# untitled.net
KiCad netlist of a schematic drawn in EAGLE
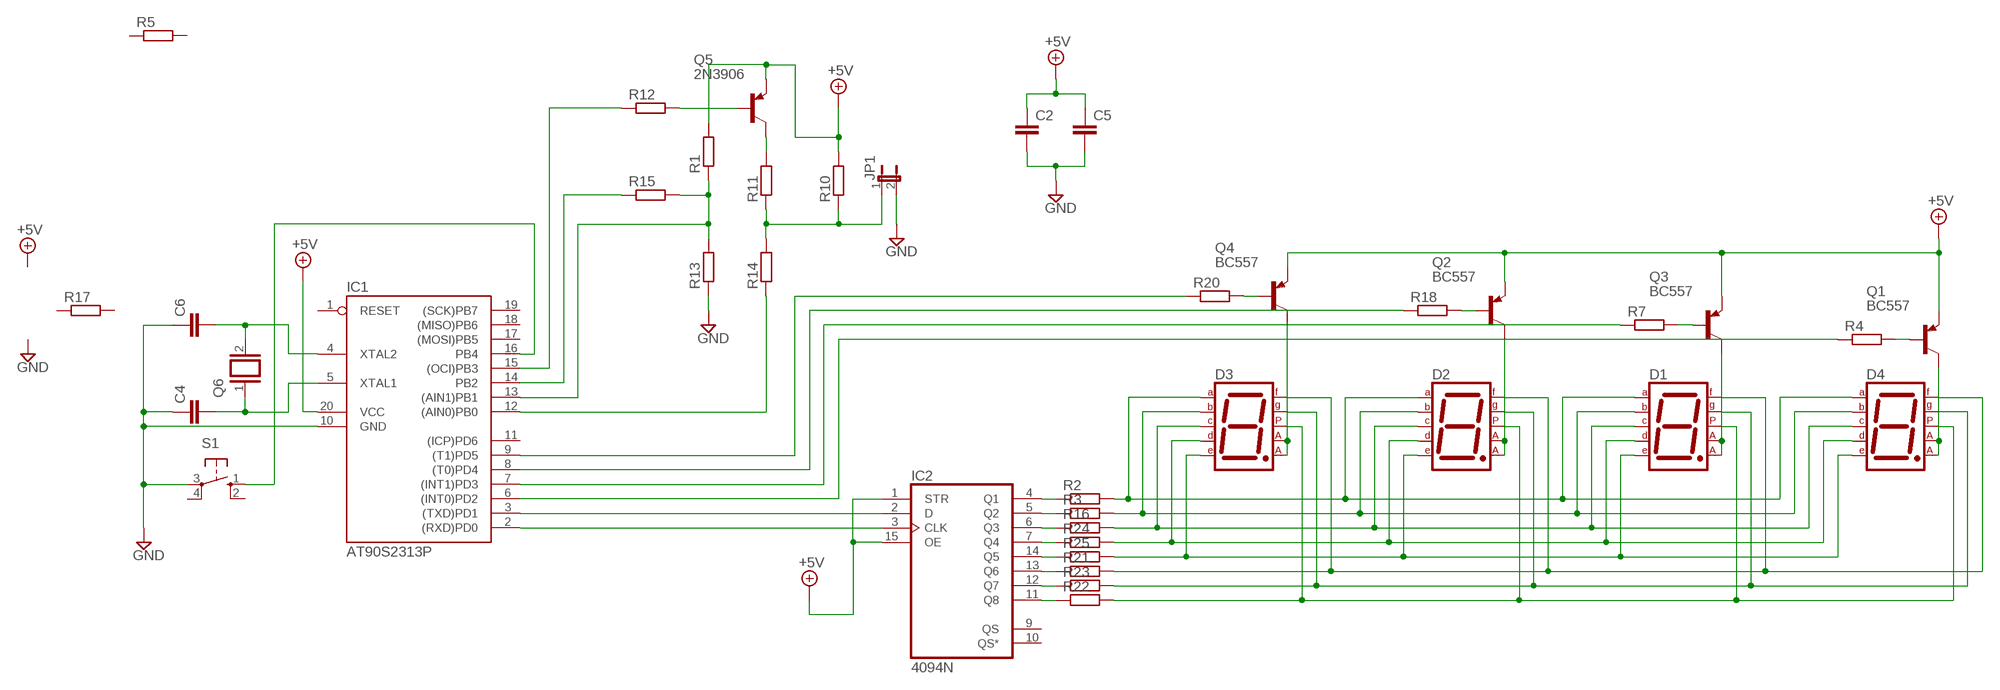
[diagram p0: schematic, sheet 1]

(export (version "E")
  (design (tool "Eeschema 10.0.6"))
  (components
    (comp (ref "C2")
      (value "C-EU025-025X050")
      (footprint "eagle-import:C025-025X050")
      (libsource (lib "eagle-import") (part "C-EU025-025X050"))
    )
    (comp (ref "C4")
      (value "C-EU025-025X050")
      (footprint "eagle-import:C025-025X050")
      (libsource (lib "eagle-import") (part "C-EU025-025X050"))
    )
    (comp (ref "C5")
      (value "C-EU025-025X050")
      (footprint "eagle-import:C025-025X050")
      (libsource (lib "eagle-import") (part "C-EU025-025X050"))
    )
    (comp (ref "C6")
      (value "C-EU025-025X050")
      (footprint "eagle-import:C025-025X050")
      (libsource (lib "eagle-import") (part "C-EU025-025X050"))
    )
    (comp (ref "D1")
      (value "7SEG-CA")
      (footprint "eagle-import:7SEG-13")
      (libsource (lib "eagle-import") (part "7SEG-CA"))
    )
    (comp (ref "D2")
      (value "7SEG-CA")
      (footprint "eagle-import:7SEG-13")
      (libsource (lib "eagle-import") (part "7SEG-CA"))
    )
    (comp (ref "D3")
      (value "7SEG-CA")
      (footprint "eagle-import:7SEG-13")
      (libsource (lib "eagle-import") (part "7SEG-CA"))
    )
    (comp (ref "D4")
      (value "7SEG-CA")
      (footprint "eagle-import:7SEG-13")
      (libsource (lib "eagle-import") (part "7SEG-CA"))
    )
    (comp (ref "IC1")
      (value "AT90S2313P")
      (footprint "eagle-import:DIL20")
      (libsource (lib "eagle-import") (part "AT90S2313P"))
    )
    (comp (ref "IC2")
      (value "4094N")
      (footprint "eagle-import:DIL16")
      (libsource (lib "eagle-import") (part "4094N"))
    )
    (comp (ref "JP1")
      (value "JP1E")
      (footprint "eagle-import:JP1")
      (libsource (lib "eagle-import") (part "JP1E"))
    )
    (comp (ref "Q1")
      (value "BC557")
      (footprint "eagle-import:TO92")
      (libsource (lib "eagle-import") (part "BC557"))
    )
    (comp (ref "Q2")
      (value "BC557")
      (footprint "eagle-import:TO92")
      (libsource (lib "eagle-import") (part "BC557"))
    )
    (comp (ref "Q3")
      (value "BC557")
      (footprint "eagle-import:TO92")
      (libsource (lib "eagle-import") (part "BC557"))
    )
    (comp (ref "Q4")
      (value "BC557")
      (footprint "eagle-import:TO92")
      (libsource (lib "eagle-import") (part "BC557"))
    )
    (comp (ref "Q5")
      (value "2N3906")
      (footprint "eagle-import:TO92")
      (libsource (lib "eagle-import") (part "2N3906"))
    )
    (comp (ref "Q6")
      (value "XTAL/S")
      (footprint "eagle-import:QS")
      (libsource (lib "eagle-import") (part "XTAL/S"))
    )
    (comp (ref "R1")
      (value "R-EU_0204/2V")
      (footprint "eagle-import:0204V")
      (libsource (lib "eagle-import") (part "R-EU_0204/2V"))
    )
    (comp (ref "R2")
      (value "R-EU_0204/7")
      (footprint "eagle-import:0204_7")
      (libsource (lib "eagle-import") (part "R-EU_0204/7"))
    )
    (comp (ref "R3")
      (value "R-EU_0204/7")
      (footprint "eagle-import:0204_7")
      (libsource (lib "eagle-import") (part "R-EU_0204/7"))
    )
    (comp (ref "R4")
      (value "R-EU_0204/7")
      (footprint "eagle-import:0204_7")
      (libsource (lib "eagle-import") (part "R-EU_0204/7"))
    )
    (comp (ref "R5")
      (value "R-EU_0204/2V")
      (footprint "eagle-import:0204V")
      (libsource (lib "eagle-import") (part "R-EU_0204/2V"))
    )
    (comp (ref "R7")
      (value "R-EU_0204/7")
      (footprint "eagle-import:0204_7")
      (libsource (lib "eagle-import") (part "R-EU_0204/7"))
    )
    (comp (ref "R10")
      (value "R-EU_0204/2V")
      (footprint "eagle-import:0204V")
      (libsource (lib "eagle-import") (part "R-EU_0204/2V"))
    )
    (comp (ref "R11")
      (value "R-EU_0204/2V")
      (footprint "eagle-import:0204V")
      (libsource (lib "eagle-import") (part "R-EU_0204/2V"))
    )
    (comp (ref "R12")
      (value "R-EU_0204/2V")
      (footprint "eagle-import:0204V")
      (libsource (lib "eagle-import") (part "R-EU_0204/2V"))
    )
    (comp (ref "R13")
      (value "R-EU_0204/2V")
      (footprint "eagle-import:0204V")
      (libsource (lib "eagle-import") (part "R-EU_0204/2V"))
    )
    (comp (ref "R14")
      (value "R-EU_0204/2V")
      (footprint "eagle-import:0204V")
      (libsource (lib "eagle-import") (part "R-EU_0204/2V"))
    )
    (comp (ref "R15")
      (value "R-EU_0204/2V")
      (footprint "eagle-import:0204V")
      (libsource (lib "eagle-import") (part "R-EU_0204/2V"))
    )
    (comp (ref "R16")
      (value "R-EU_0204/7")
      (footprint "eagle-import:0204_7")
      (libsource (lib "eagle-import") (part "R-EU_0204/7"))
    )
    (comp (ref "R17")
      (value "R-EU_0204/2V")
      (footprint "eagle-import:0204V")
      (libsource (lib "eagle-import") (part "R-EU_0204/2V"))
    )
    (comp (ref "R18")
      (value "R-EU_0204/7")
      (footprint "eagle-import:0204_7")
      (libsource (lib "eagle-import") (part "R-EU_0204/7"))
    )
    (comp (ref "R20")
      (value "R-EU_0204/7")
      (footprint "eagle-import:0204_7")
      (libsource (lib "eagle-import") (part "R-EU_0204/7"))
    )
    (comp (ref "R21")
      (value "R-EU_0207/12")
      (footprint "eagle-import:0207_12")
      (libsource (lib "eagle-import") (part "R-EU_0207/12"))
    )
    (comp (ref "R22")
      (value "R-EU_0204/7")
      (footprint "eagle-import:0204_7")
      (libsource (lib "eagle-import") (part "R-EU_0204/7"))
    )
    (comp (ref "R23")
      (value "R-EU_0207/12")
      (footprint "eagle-import:0207_12")
      (libsource (lib "eagle-import") (part "R-EU_0207/12"))
    )
    (comp (ref "R24")
      (value "R-EU_0204/7")
      (footprint "eagle-import:0204_7")
      (libsource (lib "eagle-import") (part "R-EU_0204/7"))
    )
    (comp (ref "R25")
      (value "R-EU_0204/7")
      (footprint "eagle-import:0204_7")
      (libsource (lib "eagle-import") (part "R-EU_0204/7"))
    )
    (comp (ref "S1")
      (value "10-XX")
      (footprint "eagle-import:B3F-10XX")
      (fields (field (name "MPN") "B3F-1000"))
      (libsource (lib "eagle-import") (part "10-XX"))
    )
  )
  (nets
    (net (code "1") (name "+5V") (class "Default")
      (node (ref "C2") (pin "1") (pinfunction "1_1") (pintype "passive"))
      (node (ref "C5") (pin "1") (pinfunction "1_1") (pintype "passive"))
      (node (ref "IC1") (pin "20") (pinfunction "VCC_20") (pintype "power_in"))
      (node (ref "IC2") (pin "1") (pinfunction "STR_1") (pintype "input"))
      (node (ref "IC2") (pin "15") (pinfunction "OE_15") (pintype "input"))
      (node (ref "Q1") (pin "1") (pinfunction "E_1") (pintype "passive"))
      (node (ref "Q2") (pin "1") (pinfunction "E_1") (pintype "passive"))
      (node (ref "Q3") (pin "1") (pinfunction "E_1") (pintype "passive"))
      (node (ref "Q4") (pin "1") (pinfunction "E_1") (pintype "passive"))
      (node (ref "Q5") (pin "3") (pinfunction "E_3") (pintype "passive"))
      (node (ref "R1") (pin "2") (pinfunction "2_2") (pintype "passive"))
      (node (ref "R10") (pin "2") (pinfunction "2_2") (pintype "passive"))
    )
    (net (code "2") (name "GND") (class "Default")
      (node (ref "C2") (pin "2") (pinfunction "2_2") (pintype "passive"))
      (node (ref "C4") (pin "1") (pinfunction "1_1") (pintype "passive"))
      (node (ref "C5") (pin "2") (pinfunction "2_2") (pintype "passive"))
      (node (ref "C6") (pin "1") (pinfunction "1_1") (pintype "passive"))
      (node (ref "IC1") (pin "10") (pinfunction "GND_10") (pintype "power_in"))
      (node (ref "JP1") (pin "2") (pinfunction "2_2") (pintype "passive"))
      (node (ref "R13") (pin "1") (pinfunction "1_1") (pintype "passive"))
      (node (ref "S1") (pin "3") (pinfunction "P_3") (pintype "passive"))
    )
    (net (code "3") (name "Net-(D1-A)") (class "Default")
      (node (ref "D1") (pin "7") (pinfunction "A_7") (pintype "passive"))
      (node (ref "D2") (pin "7") (pinfunction "A_7") (pintype "passive"))
      (node (ref "D3") (pin "7") (pinfunction "A_7") (pintype "passive"))
      (node (ref "D4") (pin "7") (pinfunction "A_7") (pintype "passive"))
      (node (ref "R2") (pin "2") (pinfunction "2_2") (pintype "passive"))
    )
    (net (code "4") (name "Net-(D1-B)") (class "Default")
      (node (ref "D1") (pin "6") (pinfunction "B_6") (pintype "passive"))
      (node (ref "D2") (pin "6") (pinfunction "B_6") (pintype "passive"))
      (node (ref "D3") (pin "6") (pinfunction "B_6") (pintype "passive"))
      (node (ref "D4") (pin "6") (pinfunction "B_6") (pintype "passive"))
      (node (ref "R3") (pin "2") (pinfunction "2_2") (pintype "passive"))
    )
    (net (code "5") (name "Net-(D1-C)") (class "Default")
      (node (ref "D1") (pin "4") (pinfunction "C_4") (pintype "passive"))
      (node (ref "D2") (pin "4") (pinfunction "C_4") (pintype "passive"))
      (node (ref "D3") (pin "4") (pinfunction "C_4") (pintype "passive"))
      (node (ref "D4") (pin "4") (pinfunction "C_4") (pintype "passive"))
      (node (ref "R16") (pin "2") (pinfunction "2_2") (pintype "passive"))
    )
    (net (code "6") (name "Net-(D1-CA1)") (class "Default")
      (node (ref "D1") (pin "3") (pinfunction "CA1_3") (pintype "passive"))
      (node (ref "D1") (pin "8") (pinfunction "CA2_8") (pintype "passive"))
      (node (ref "Q3") (pin "3") (pinfunction "C_3") (pintype "passive"))
    )
    (net (code "7") (name "Net-(D1-D)") (class "Default")
      (node (ref "D1") (pin "2") (pinfunction "D_2") (pintype "passive"))
      (node (ref "D2") (pin "2") (pinfunction "D_2") (pintype "passive"))
      (node (ref "D3") (pin "2") (pinfunction "D_2") (pintype "passive"))
      (node (ref "D4") (pin "2") (pinfunction "D_2") (pintype "passive"))
      (node (ref "R24") (pin "2") (pinfunction "2_2") (pintype "passive"))
    )
    (net (code "8") (name "Net-(D1-DP)") (class "Default")
      (node (ref "D1") (pin "5") (pinfunction "DP_5") (pintype "passive"))
      (node (ref "D2") (pin "5") (pinfunction "DP_5") (pintype "passive"))
      (node (ref "D3") (pin "5") (pinfunction "DP_5") (pintype "passive"))
      (node (ref "D4") (pin "5") (pinfunction "DP_5") (pintype "passive"))
      (node (ref "R22") (pin "2") (pinfunction "2_2") (pintype "passive"))
    )
    (net (code "9") (name "Net-(D1-E)") (class "Default")
      (node (ref "D1") (pin "1") (pinfunction "E_1") (pintype "passive"))
      (node (ref "D2") (pin "1") (pinfunction "E_1") (pintype "passive"))
      (node (ref "D3") (pin "1") (pinfunction "E_1") (pintype "passive"))
      (node (ref "D4") (pin "1") (pinfunction "E_1") (pintype "passive"))
      (node (ref "R25") (pin "2") (pinfunction "2_2") (pintype "passive"))
    )
    (net (code "10") (name "Net-(D1-F)") (class "Default")
      (node (ref "D1") (pin "9") (pinfunction "F_9") (pintype "passive"))
      (node (ref "D2") (pin "9") (pinfunction "F_9") (pintype "passive"))
      (node (ref "D3") (pin "9") (pinfunction "F_9") (pintype "passive"))
      (node (ref "D4") (pin "9") (pinfunction "F_9") (pintype "passive"))
      (node (ref "R21") (pin "2") (pinfunction "2_2") (pintype "passive"))
    )
    (net (code "11") (name "Net-(D1-G)") (class "Default")
      (node (ref "D1") (pin "10") (pinfunction "G_10") (pintype "passive"))
      (node (ref "D2") (pin "10") (pinfunction "G_10") (pintype "passive"))
      (node (ref "D3") (pin "10") (pinfunction "G_10") (pintype "passive"))
      (node (ref "D4") (pin "10") (pinfunction "G_10") (pintype "passive"))
      (node (ref "R23") (pin "2") (pinfunction "2_2") (pintype "passive"))
    )
    (net (code "12") (name "Net-(D2-CA1)") (class "Default")
      (node (ref "D2") (pin "3") (pinfunction "CA1_3") (pintype "passive"))
      (node (ref "D2") (pin "8") (pinfunction "CA2_8") (pintype "passive"))
      (node (ref "Q2") (pin "3") (pinfunction "C_3") (pintype "passive"))
    )
    (net (code "13") (name "Net-(D3-CA1)") (class "Default")
      (node (ref "D3") (pin "3") (pinfunction "CA1_3") (pintype "passive"))
      (node (ref "D3") (pin "8") (pinfunction "CA2_8") (pintype "passive"))
      (node (ref "Q4") (pin "3") (pinfunction "C_3") (pintype "passive"))
    )
    (net (code "14") (name "Net-(D4-CA1)") (class "Default")
      (node (ref "D4") (pin "3") (pinfunction "CA1_3") (pintype "passive"))
      (node (ref "D4") (pin "8") (pinfunction "CA2_8") (pintype "passive"))
      (node (ref "Q1") (pin "3") (pinfunction "C_3") (pintype "passive"))
    )
    (net (code "15") (name "Net-(IC1-(AIN0)PB0)") (class "Default")
      (node (ref "IC1") (pin "12") (pinfunction "(AIN0)PB0_12") (pintype "bidirectional"))
      (node (ref "R14") (pin "1") (pinfunction "1_1") (pintype "passive"))
    )
    (net (code "16") (name "Net-(IC1-(AIN1)PB1)") (class "Default")
      (node (ref "IC1") (pin "13") (pinfunction "(AIN1)PB1_13") (pintype "bidirectional"))
      (node (ref "R1") (pin "1") (pinfunction "1_1") (pintype "passive"))
      (node (ref "R13") (pin "2") (pinfunction "2_2") (pintype "passive"))
      (node (ref "R15") (pin "2") (pinfunction "2_2") (pintype "passive"))
    )
    (net (code "17") (name "Net-(IC1-(INT0)PD2)") (class "Default")
      (node (ref "IC1") (pin "6") (pinfunction "(INT0)PD2_6") (pintype "bidirectional"))
      (node (ref "R4") (pin "1") (pinfunction "1_1") (pintype "passive"))
    )
    (net (code "18") (name "Net-(IC1-(INT1)PD3)") (class "Default")
      (node (ref "IC1") (pin "7") (pinfunction "(INT1)PD3_7") (pintype "bidirectional"))
      (node (ref "R7") (pin "1") (pinfunction "1_1") (pintype "passive"))
    )
    (net (code "19") (name "Net-(IC1-(OCI)PB3)") (class "Default")
      (node (ref "IC1") (pin "15") (pinfunction "(OCI)PB3_15") (pintype "bidirectional"))
      (node (ref "R12") (pin "1") (pinfunction "1_1") (pintype "passive"))
    )
    (net (code "20") (name "Net-(IC1-(RXD)PD0)") (class "Default")
      (node (ref "IC1") (pin "2") (pinfunction "(RXD)PD0_2") (pintype "bidirectional"))
      (node (ref "IC2") (pin "3") (pinfunction "CLK_3") (pintype "input"))
    )
    (net (code "21") (name "Net-(IC1-(T0)PD4)") (class "Default")
      (node (ref "IC1") (pin "8") (pinfunction "(T0)PD4_8") (pintype "bidirectional"))
      (node (ref "R18") (pin "1") (pinfunction "1_1") (pintype "passive"))
    )
    (net (code "22") (name "Net-(IC1-(T1)PD5)") (class "Default")
      (node (ref "IC1") (pin "9") (pinfunction "(T1)PD5_9") (pintype "bidirectional"))
      (node (ref "R20") (pin "1") (pinfunction "1_1") (pintype "passive"))
    )
    (net (code "23") (name "Net-(IC1-(TXD)PD1)") (class "Default")
      (node (ref "IC1") (pin "3") (pinfunction "(TXD)PD1_3") (pintype "bidirectional"))
      (node (ref "IC2") (pin "2") (pinfunction "D_2") (pintype "input"))
    )
    (net (code "24") (name "Net-(IC1-PB2)") (class "Default")
      (node (ref "IC1") (pin "14") (pinfunction "PB2_14") (pintype "bidirectional"))
      (node (ref "R15") (pin "1") (pinfunction "1_1") (pintype "passive"))
    )
    (net (code "25") (name "Net-(IC1-PB4)") (class "Default")
      (node (ref "IC1") (pin "16") (pinfunction "PB4_16") (pintype "bidirectional"))
      (node (ref "S1") (pin "1") (pinfunction "S_1") (pintype "passive"))
    )
    (net (code "26") (name "Net-(IC1-XTAL1)") (class "Default")
      (node (ref "C4") (pin "2") (pinfunction "2_2") (pintype "passive"))
      (node (ref "IC1") (pin "5") (pinfunction "XTAL1_5") (pintype "bidirectional"))
      (node (ref "Q6") (pin "1") (pinfunction "1_1") (pintype "passive"))
    )
    (net (code "27") (name "Net-(IC1-XTAL2)") (class "Default")
      (node (ref "C6") (pin "2") (pinfunction "2_2") (pintype "passive"))
      (node (ref "IC1") (pin "4") (pinfunction "XTAL2_4") (pintype "bidirectional"))
      (node (ref "Q6") (pin "2") (pinfunction "2_2") (pintype "passive"))
    )
    (net (code "28") (name "Net-(IC2A-Q1)") (class "Default")
      (node (ref "IC2") (pin "4") (pinfunction "Q1_4") (pintype "output"))
      (node (ref "R2") (pin "1") (pinfunction "1_1") (pintype "passive"))
    )
    (net (code "29") (name "Net-(IC2A-Q2)") (class "Default")
      (node (ref "IC2") (pin "5") (pinfunction "Q2_5") (pintype "output"))
      (node (ref "R3") (pin "1") (pinfunction "1_1") (pintype "passive"))
    )
    (net (code "30") (name "Net-(IC2A-Q3)") (class "Default")
      (node (ref "IC2") (pin "6") (pinfunction "Q3_6") (pintype "output"))
      (node (ref "R16") (pin "1") (pinfunction "1_1") (pintype "passive"))
    )
    (net (code "31") (name "Net-(IC2A-Q4)") (class "Default")
      (node (ref "IC2") (pin "7") (pinfunction "Q4_7") (pintype "output"))
      (node (ref "R24") (pin "1") (pinfunction "1_1") (pintype "passive"))
    )
    (net (code "32") (name "Net-(IC2A-Q5)") (class "Default")
      (node (ref "IC2") (pin "14") (pinfunction "Q5_14") (pintype "output"))
      (node (ref "R25") (pin "1") (pinfunction "1_1") (pintype "passive"))
    )
    (net (code "33") (name "Net-(IC2A-Q6)") (class "Default")
      (node (ref "IC2") (pin "13") (pinfunction "Q6_13") (pintype "output"))
      (node (ref "R21") (pin "1") (pinfunction "1_1") (pintype "passive"))
    )
    (net (code "34") (name "Net-(IC2A-Q7)") (class "Default")
      (node (ref "IC2") (pin "12") (pinfunction "Q7_12") (pintype "output"))
      (node (ref "R23") (pin "1") (pinfunction "1_1") (pintype "passive"))
    )
    (net (code "35") (name "Net-(IC2A-Q8)") (class "Default")
      (node (ref "IC2") (pin "11") (pinfunction "Q8_11") (pintype "output"))
      (node (ref "R22") (pin "1") (pinfunction "1_1") (pintype "passive"))
    )
    (net (code "36") (name "Net-(JP1-Pad1)") (class "Default")
      (node (ref "JP1") (pin "1") (pinfunction "1_1") (pintype "passive"))
      (node (ref "R10") (pin "1") (pinfunction "1_1") (pintype "passive"))
      (node (ref "R11") (pin "1") (pinfunction "1_1") (pintype "passive"))
      (node (ref "R14") (pin "2") (pinfunction "2_2") (pintype "passive"))
    )
    (net (code "37") (name "Net-(Q1-B)") (class "Default")
      (node (ref "Q1") (pin "2") (pinfunction "B_2") (pintype "passive"))
      (node (ref "R4") (pin "2") (pinfunction "2_2") (pintype "passive"))
    )
    (net (code "38") (name "Net-(Q2-B)") (class "Default")
      (node (ref "Q2") (pin "2") (pinfunction "B_2") (pintype "passive"))
      (node (ref "R18") (pin "2") (pinfunction "2_2") (pintype "passive"))
    )
    (net (code "39") (name "Net-(Q3-B)") (class "Default")
      (node (ref "Q3") (pin "2") (pinfunction "B_2") (pintype "passive"))
      (node (ref "R7") (pin "2") (pinfunction "2_2") (pintype "passive"))
    )
    (net (code "40") (name "Net-(Q4-B)") (class "Default")
      (node (ref "Q4") (pin "2") (pinfunction "B_2") (pintype "passive"))
      (node (ref "R20") (pin "2") (pinfunction "2_2") (pintype "passive"))
    )
    (net (code "41") (name "Net-(Q5-B)") (class "Default")
      (node (ref "Q5") (pin "2") (pinfunction "B_2") (pintype "passive"))
      (node (ref "R12") (pin "2") (pinfunction "2_2") (pintype "passive"))
    )
    (net (code "42") (name "Net-(Q5-C)") (class "Default")
      (node (ref "Q5") (pin "1") (pinfunction "C_1") (pintype "passive"))
      (node (ref "R11") (pin "2") (pinfunction "2_2") (pintype "passive"))
    )
    (net (code "43") (name "unconnected-(IC1-(ICP)PD6-Pad11)") (class "Default")
      (node (ref "IC1") (pin "11") (pinfunction "(ICP)PD6_11") (pintype "bidirectional"))
    )
    (net (code "44") (name "unconnected-(IC1-(MISO)PB6-Pad18)") (class "Default")
      (node (ref "IC1") (pin "18") (pinfunction "(MISO)PB6_18") (pintype "bidirectional"))
    )
    (net (code "45") (name "unconnected-(IC1-(MOSI)PB5-Pad17)") (class "Default")
      (node (ref "IC1") (pin "17") (pinfunction "(MOSI)PB5_17") (pintype "bidirectional"))
    )
    (net (code "46") (name "unconnected-(IC1-(SCK)PB7-Pad19)") (class "Default")
      (node (ref "IC1") (pin "19") (pinfunction "(SCK)PB7_19") (pintype "bidirectional"))
    )
    (net (code "47") (name "unconnected-(IC1-RESET-Pad1)") (class "Default")
      (node (ref "IC1") (pin "1") (pinfunction "RESET_1") (pintype "bidirectional"))
    )
    (net (code "48") (name "unconnected-(IC2A-QS*-Pad10)") (class "Default")
      (node (ref "IC2") (pin "10") (pinfunction "QS*_10") (pintype "output"))
    )
    (net (code "49") (name "unconnected-(IC2A-QS-Pad9)") (class "Default")
      (node (ref "IC2") (pin "9") (pinfunction "QS_9") (pintype "output"))
    )
    (net (code "50") (name "unconnected-(R5-Pad1)") (class "Default")
      (node (ref "R5") (pin "1") (pinfunction "1_1") (pintype "passive"))
    )
    (net (code "51") (name "unconnected-(R5-Pad2)") (class "Default")
      (node (ref "R5") (pin "2") (pinfunction "2_2") (pintype "passive"))
    )
    (net (code "52") (name "unconnected-(R17-Pad1)") (class "Default")
      (node (ref "R17") (pin "1") (pinfunction "1_1") (pintype "passive"))
    )
    (net (code "53") (name "unconnected-(R17-Pad2)") (class "Default")
      (node (ref "R17") (pin "2") (pinfunction "2_2") (pintype "passive"))
    )
    (net (code "54") (name "unconnected-(S1-P1-Pad4)") (class "Default")
      (node (ref "S1") (pin "4") (pinfunction "P1_4") (pintype "passive"))
    )
    (net (code "55") (name "unconnected-(S1-S1-Pad2)") (class "Default")
      (node (ref "S1") (pin "2") (pinfunction "S1_2") (pintype "passive"))
    )
  )
)
